# WIZ500SR-RP-EVB_RJ45.net
KiCad netlist of a schematic drawn in Altium Designer
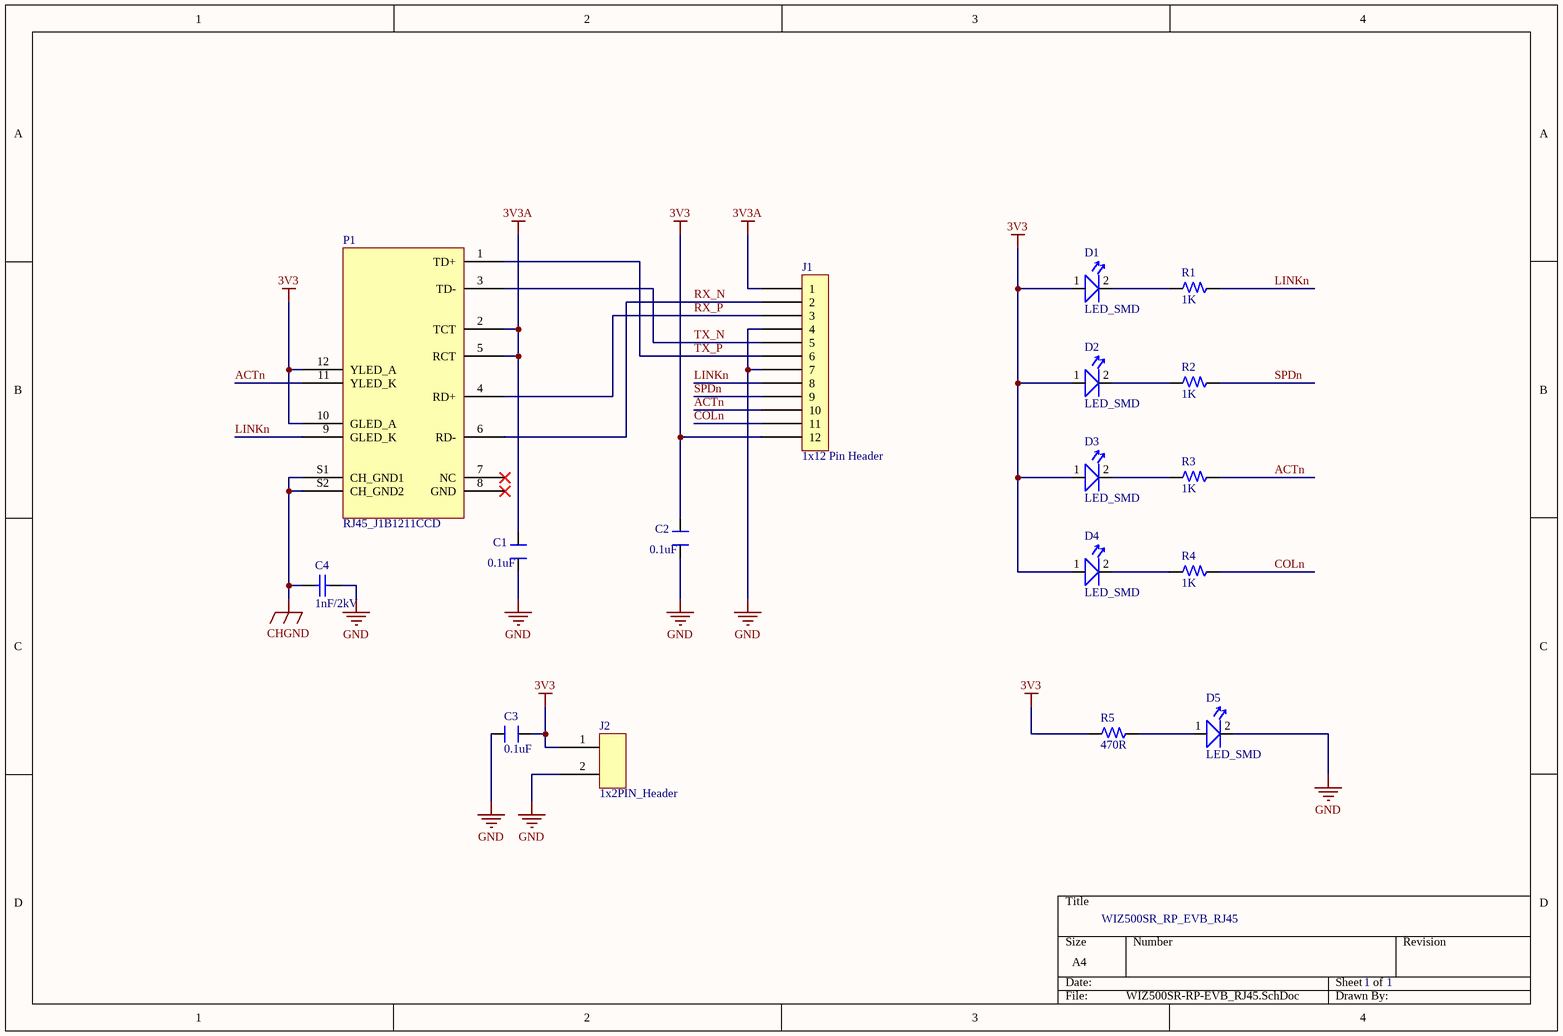
[diagram p0: WIZ500SR-RP-EVB_RJ45.SchDoc]

(export (version "E")
  (design (tool "Eeschema 10.0.6"))
  (components
    (comp (ref "C1")
      (value "0.1uF")
      (footprint "CAP_0603")
      (libsource (lib "Integrated_Library1") (part "Cap"))
    )
    (comp (ref "C2")
      (value "0.1uF")
      (footprint "CAP_0603")
      (libsource (lib "Integrated_Library1") (part "Cap"))
    )
    (comp (ref "C3")
      (value "0.1uF")
      (footprint "CAP_0603")
      (libsource (lib "Integrated_Library1") (part "Cap"))
    )
    (comp (ref "C4")
      (value "1nF/2kV")
      (footprint "CAPC4620X180X75LL50T35")
      (description "Chip Capacitor, 1000 pF, +/- 10%, 2000 V, -55 to 125 degC, 1808 (4520 Metric), RoHS, Tape and Reel")
      (fields (field (name "MANUFACTURER") "AVX"))
      (libsource (lib "Altium Content Vault") (part "CAP-NP-2"))
    )
    (comp (ref "D1")
      (value "LED_SMD")
      (footprint "LED-0603-RED")
      (libsource (lib "Integrated_Library1") (part "LED_SMD"))
    )
    (comp (ref "D2")
      (value "LED_SMD")
      (footprint "LED-0603-RED")
      (libsource (lib "Integrated_Library1") (part "LED_SMD"))
    )
    (comp (ref "D3")
      (value "LED_SMD")
      (footprint "LED-0603-RED")
      (libsource (lib "Integrated_Library1") (part "LED_SMD"))
    )
    (comp (ref "D4")
      (value "LED_SMD")
      (footprint "LED-0603-RED")
      (libsource (lib "Integrated_Library1") (part "LED_SMD"))
    )
    (comp (ref "D5")
      (value "LED_SMD")
      (footprint "LED-0603-RED")
      (libsource (lib "Integrated_Library1") (part "LED_SMD"))
    )
    (comp (ref "J1")
      (value "1x12 Pin Header")
      (footprint "12PIN_HEADER_2mm")
      (libsource (lib "Integrated_Library1") (part "12PIN_2mm"))
    )
    (comp (ref "J2")
      (value "1x2PIN_Header")
      (footprint "2PIN_HEADER")
      (libsource (lib "Integrated_Library1") (part "2PIN"))
    )
    (comp (ref "P1")
      (value "RJ45_J1B1211CCD")
      (footprint "RJ45-J1B1211CCD")
      (libsource (lib "Integrated_Library1") (part "RJ45_J1B1211CCD"))
    )
    (comp (ref "R1")
      (value "1K")
      (footprint "RES-0603")
      (libsource (lib "Integrated_Library1") (part "Res_(SMD)"))
    )
    (comp (ref "R2")
      (value "1K")
      (footprint "RES-0603")
      (libsource (lib "Integrated_Library1") (part "Res_(SMD)"))
    )
    (comp (ref "R3")
      (value "1K")
      (footprint "RES-0603")
      (libsource (lib "Integrated_Library1") (part "Res_(SMD)"))
    )
    (comp (ref "R4")
      (value "1K")
      (footprint "RES-0603")
      (libsource (lib "Integrated_Library1") (part "Res_(SMD)"))
    )
    (comp (ref "R5")
      (value "470R")
      (footprint "RES-0603")
      (libsource (lib "Integrated_Library1") (part "Res_(SMD)"))
    )
  )
  (nets
    (net (code "1") (name "/ACTn") (class "Default")
      (node (ref "J1") (pin "10") (pinfunction "10_10") (pintype "passive"))
      (node (ref "P1") (pin "11") (pinfunction "YLED_K_11") (pintype "passive"))
      (node (ref "R3") (pin "2") (pinfunction "2_2") (pintype "passive"))
    )
    (net (code "2") (name "/COLn") (class "Default")
      (node (ref "J1") (pin "11") (pinfunction "11_11") (pintype "passive"))
      (node (ref "R4") (pin "2") (pinfunction "2_2") (pintype "passive"))
    )
    (net (code "3") (name "/LINKn") (class "Default")
      (node (ref "J1") (pin "8") (pinfunction "8_8") (pintype "passive"))
      (node (ref "P1") (pin "9") (pinfunction "GLED_K_9") (pintype "passive"))
      (node (ref "R1") (pin "2") (pinfunction "2_2") (pintype "passive"))
    )
    (net (code "4") (name "/RX_N") (class "Default")
      (node (ref "J1") (pin "2") (pinfunction "2_2") (pintype "passive"))
      (node (ref "P1") (pin "6") (pinfunction "RD-_6") (pintype "passive"))
    )
    (net (code "5") (name "/RX_P") (class "Default")
      (node (ref "J1") (pin "3") (pinfunction "3_3") (pintype "passive"))
      (node (ref "P1") (pin "4") (pinfunction "RD+_4") (pintype "passive"))
    )
    (net (code "6") (name "/SPDn") (class "Default")
      (node (ref "J1") (pin "9") (pinfunction "9_9") (pintype "passive"))
      (node (ref "R2") (pin "2") (pinfunction "2_2") (pintype "passive"))
    )
    (net (code "7") (name "/TX_N") (class "Default")
      (node (ref "J1") (pin "5") (pinfunction "5_5") (pintype "passive"))
      (node (ref "P1") (pin "3") (pinfunction "TD-_3") (pintype "passive"))
    )
    (net (code "8") (name "/TX_P") (class "Default")
      (node (ref "J1") (pin "6") (pinfunction "6_6") (pintype "passive"))
      (node (ref "P1") (pin "1") (pinfunction "TD+_1") (pintype "passive"))
    )
    (net (code "9") (name "3V3") (class "Default")
      (node (ref "C2") (pin "2") (pintype "passive"))
      (node (ref "C3") (pin "1") (pintype "passive"))
      (node (ref "D1") (pin "1") (pintype "passive"))
      (node (ref "D2") (pin "1") (pintype "passive"))
      (node (ref "D3") (pin "1") (pintype "passive"))
      (node (ref "D4") (pin "1") (pintype "passive"))
      (node (ref "J1") (pin "12") (pinfunction "12_12") (pintype "passive"))
      (node (ref "J2") (pin "1") (pintype "passive"))
      (node (ref "P1") (pin "10") (pinfunction "GLED_A_10") (pintype "passive"))
      (node (ref "P1") (pin "12") (pinfunction "YLED_A_12") (pintype "passive"))
      (node (ref "R5") (pin "1") (pinfunction "1_1") (pintype "passive"))
    )
    (net (code "10") (name "3V3A") (class "Default")
      (node (ref "C1") (pin "2") (pintype "passive"))
      (node (ref "J1") (pin "1") (pinfunction "1_1") (pintype "passive"))
      (node (ref "P1") (pin "2") (pinfunction "TCT_2") (pintype "passive"))
      (node (ref "P1") (pin "5") (pinfunction "RCT_5") (pintype "passive"))
    )
    (net (code "11") (name "CHGND") (class "Default")
      (node (ref "C4") (pin "1") (pinfunction "1_1") (pintype "passive"))
      (node (ref "P1") (pin "S1") (pinfunction "CH_GND1_S1") (pintype "passive"))
      (node (ref "P1") (pin "S2") (pinfunction "CH_GND2_S2") (pintype "passive"))
    )
    (net (code "12") (name "GND") (class "Default")
      (node (ref "C1") (pin "1") (pintype "passive"))
      (node (ref "C2") (pin "1") (pintype "passive"))
      (node (ref "C3") (pin "2") (pintype "passive"))
      (node (ref "C4") (pin "2") (pinfunction "2_2") (pintype "passive"))
      (node (ref "D5") (pin "2") (pintype "passive"))
      (node (ref "J1") (pin "4") (pinfunction "4_4") (pintype "passive"))
      (node (ref "J1") (pin "7") (pinfunction "7_7") (pintype "passive"))
      (node (ref "J2") (pin "2") (pintype "passive"))
    )
    (net (code "13") (name "Net-(D1-Pad2)") (class "Default")
      (node (ref "D1") (pin "2") (pintype "passive"))
      (node (ref "R1") (pin "1") (pinfunction "1_1") (pintype "passive"))
    )
    (net (code "14") (name "Net-(D2-Pad2)") (class "Default")
      (node (ref "D2") (pin "2") (pintype "passive"))
      (node (ref "R2") (pin "1") (pinfunction "1_1") (pintype "passive"))
    )
    (net (code "15") (name "Net-(D3-Pad2)") (class "Default")
      (node (ref "D3") (pin "2") (pintype "passive"))
      (node (ref "R3") (pin "1") (pinfunction "1_1") (pintype "passive"))
    )
    (net (code "16") (name "Net-(D4-Pad2)") (class "Default")
      (node (ref "D4") (pin "2") (pintype "passive"))
      (node (ref "R4") (pin "1") (pinfunction "1_1") (pintype "passive"))
    )
    (net (code "17") (name "Net-(D5-Pad1)") (class "Default")
      (node (ref "D5") (pin "1") (pintype "passive"))
      (node (ref "R5") (pin "2") (pinfunction "2_2") (pintype "passive"))
    )
    (net (code "18") (name "unconnected-(P1-GND-Pad8)") (class "Default")
      (node (ref "P1") (pin "8") (pinfunction "GND_8") (pintype "passive+no_connect"))
    )
    (net (code "19") (name "unconnected-(P1-NC-Pad7)") (class "Default")
      (node (ref "P1") (pin "7") (pinfunction "NC_7") (pintype "passive+no_connect"))
    )
  )
)
